# business_card.net
KiCad netlist of a schematic drawn in EAGLE
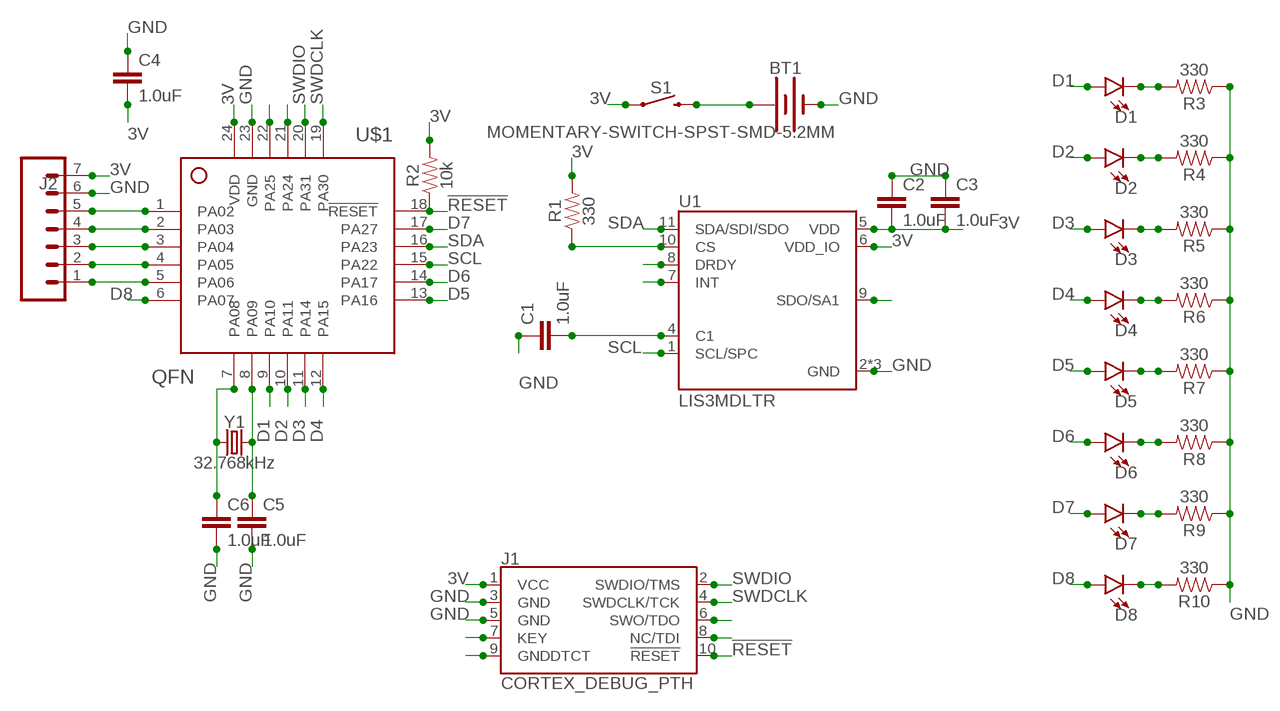
[diagram p0: schematic, sheet 1]

(export (version "E")
  (design (tool "Eeschema 10.0.6"))
  (components
    (comp (ref "BT1")
      (value "BATTERY-20MM_SMD_4LEGS")
      (footprint "eagle-import:BATTCON_20MM_4LEGS")
      (libsource (lib "eagle-import") (part "BATTERY-20MM_SMD_4LEGS"))
    )
    (comp (ref "C1")
      (value "1.0uF")
      (footprint "eagle-import:0402")
      (libsource (lib "eagle-import") (part "1.0UF-0402-16V-10%"))
    )
    (comp (ref "C2")
      (value "1.0uF")
      (footprint "eagle-import:0402")
      (libsource (lib "eagle-import") (part "1.0UF-0402-16V-10%"))
    )
    (comp (ref "C3")
      (value "1.0uF")
      (footprint "eagle-import:0402")
      (libsource (lib "eagle-import") (part "1.0UF-0402-16V-10%"))
    )
    (comp (ref "C4")
      (value "1.0uF")
      (footprint "eagle-import:0402")
      (libsource (lib "eagle-import") (part "1.0UF-0402-16V-10%"))
    )
    (comp (ref "C5")
      (value "1.0uF")
      (footprint "eagle-import:0402")
      (libsource (lib "eagle-import") (part "1.0UF-0402-16V-10%"))
    )
    (comp (ref "C6")
      (value "1.0uF")
      (footprint "eagle-import:0402")
      (libsource (lib "eagle-import") (part "1.0UF-0402-16V-10%"))
    )
    (comp (ref "D1")
      (value "LED0603")
      (footprint "eagle-import:LED-0603")
      (libsource (lib "eagle-import") (part "LED0603"))
    )
    (comp (ref "D2")
      (value "LED0603")
      (footprint "eagle-import:LED-0603")
      (libsource (lib "eagle-import") (part "LED0603"))
    )
    (comp (ref "D3")
      (value "LED0603")
      (footprint "eagle-import:LED-0603")
      (libsource (lib "eagle-import") (part "LED0603"))
    )
    (comp (ref "D4")
      (value "LED0603")
      (footprint "eagle-import:LED-0603")
      (libsource (lib "eagle-import") (part "LED0603"))
    )
    (comp (ref "D5")
      (value "LED0603")
      (footprint "eagle-import:LED-0603")
      (libsource (lib "eagle-import") (part "LED0603"))
    )
    (comp (ref "D6")
      (value "LED0603")
      (footprint "eagle-import:LED-0603")
      (libsource (lib "eagle-import") (part "LED0603"))
    )
    (comp (ref "D7")
      (value "LED0603")
      (footprint "eagle-import:LED-0603")
      (libsource (lib "eagle-import") (part "LED0603"))
    )
    (comp (ref "D8")
      (value "LED0603")
      (footprint "eagle-import:LED-0603")
      (libsource (lib "eagle-import") (part "LED0603"))
    )
    (comp (ref "J1")
      (value "CORTEX_DEBUG_PTH")
      (footprint "eagle-import:2X5-PTH-1.27MM")
      (libsource (lib "eagle-import") (part "CORTEX_DEBUG_PTH"))
    )
    (comp (ref "J2")
      (value "CONN_07")
      (footprint "eagle-import:1X07")
      (libsource (lib "eagle-import") (part "CONN_07"))
    )
    (comp (ref "R1")
      (value "330")
      (footprint "eagle-import:0603")
      (libsource (lib "eagle-import") (part "330OHM-0603-1/10W-1%"))
    )
    (comp (ref "R2")
      (value "10k")
      (footprint "eagle-import:0603")
      (libsource (lib "eagle-import") (part "330OHM-0603-1/10W-1%"))
    )
    (comp (ref "R3")
      (value "330")
      (footprint "eagle-import:0603")
      (libsource (lib "eagle-import") (part "330OHM-0603-1/10W-1%"))
    )
    (comp (ref "R4")
      (value "330")
      (footprint "eagle-import:0603")
      (libsource (lib "eagle-import") (part "330OHM-0603-1/10W-1%"))
    )
    (comp (ref "R5")
      (value "330")
      (footprint "eagle-import:0603")
      (libsource (lib "eagle-import") (part "330OHM-0603-1/10W-1%"))
    )
    (comp (ref "R6")
      (value "330")
      (footprint "eagle-import:0603")
      (libsource (lib "eagle-import") (part "330OHM-0603-1/10W-1%"))
    )
    (comp (ref "R7")
      (value "330")
      (footprint "eagle-import:0603")
      (libsource (lib "eagle-import") (part "330OHM-0603-1/10W-1%"))
    )
    (comp (ref "R8")
      (value "330")
      (footprint "eagle-import:0603")
      (libsource (lib "eagle-import") (part "330OHM-0603-1/10W-1%"))
    )
    (comp (ref "R9")
      (value "330")
      (footprint "eagle-import:0603")
      (libsource (lib "eagle-import") (part "330OHM-0603-1/10W-1%"))
    )
    (comp (ref "R10")
      (value "330")
      (footprint "eagle-import:0603")
      (libsource (lib "eagle-import") (part "330OHM-0603-1/10W-1%"))
    )
    (comp (ref "S1")
      (value "MOMENTARY-SWITCH-SPST-SMD-5.2MM")
      (footprint "eagle-import:TACTILE_SWITCH_SMD_5.2MM")
      (libsource (lib "eagle-import") (part "MOMENTARY-SWITCH-SPST-SMD-5.2MM"))
    )
    (comp (ref "U$1")
      (value "QFN")
      (footprint "eagle-import:QFN24-4X4")
      (libsource (lib "eagle-import") (part "QFN"))
    )
    (comp (ref "U1")
      (value "LIS3MDLTR")
      (footprint "eagle-import:LGA12R50P4X4_200X200X100")
      (fields (field (name "MF") "STMicroelectronics"))
      (libsource (lib "eagle-import") (part "LIS3MDLTR"))
    )
    (comp (ref "Y1")
      (value "32.768kHz")
      (footprint "eagle-import:CRYSTAL-SMD-3.2X1.5MM")
      (libsource (lib "eagle-import") (part "CRYSTAL-32.768KHZSMD-3.2X1.5"))
    )
  )
  (nets
    (net (code "1") (name "/3V") (class "Default")
      (node (ref "C2") (pin "2") (pinfunction "2_2") (pintype "passive"))
      (node (ref "C3") (pin "2") (pinfunction "2_2") (pintype "passive"))
      (node (ref "C4") (pin "2") (pinfunction "2_2") (pintype "passive"))
      (node (ref "J1") (pin "1") (pinfunction "VCC_1") (pintype "bidirectional"))
      (node (ref "J2") (pin "7") (pinfunction "7_7") (pintype "passive"))
      (node (ref "R1") (pin "2") (pinfunction "2_2") (pintype "passive"))
      (node (ref "R2") (pin "2") (pinfunction "2_2") (pintype "passive"))
      (node (ref "S1") (pin "1") (pinfunction "1_1") (pintype "passive"))
      (node (ref "U$1") (pin "24") (pinfunction "VDD_24") (pintype "bidirectional"))
      (node (ref "U1") (pin "5") (pinfunction "VDD_5") (pintype "power_in"))
      (node (ref "U1") (pin "6") (pinfunction "VDD_IO_6") (pintype "power_in"))
    )
    (net (code "2") (name "/D1") (class "Default")
      (node (ref "D1") (pin "A") (pinfunction "A_A") (pintype "passive"))
      (node (ref "U$1") (pin "9") (pinfunction "PA10_9") (pintype "bidirectional"))
    )
    (net (code "3") (name "/D2") (class "Default")
      (node (ref "D2") (pin "A") (pinfunction "A_A") (pintype "passive"))
      (node (ref "U$1") (pin "10") (pinfunction "PA11_10") (pintype "bidirectional"))
    )
    (net (code "4") (name "/D3") (class "Default")
      (node (ref "D3") (pin "A") (pinfunction "A_A") (pintype "passive"))
      (node (ref "U$1") (pin "11") (pinfunction "PA14_11") (pintype "bidirectional"))
    )
    (net (code "5") (name "/D4") (class "Default")
      (node (ref "D4") (pin "A") (pinfunction "A_A") (pintype "passive"))
      (node (ref "U$1") (pin "12") (pinfunction "PA15_12") (pintype "bidirectional"))
    )
    (net (code "6") (name "/D5") (class "Default")
      (node (ref "D5") (pin "A") (pinfunction "A_A") (pintype "passive"))
      (node (ref "U$1") (pin "13") (pinfunction "PA16_13") (pintype "bidirectional"))
    )
    (net (code "7") (name "/D6") (class "Default")
      (node (ref "D6") (pin "A") (pinfunction "A_A") (pintype "passive"))
      (node (ref "U$1") (pin "14") (pinfunction "PA17_14") (pintype "bidirectional"))
    )
    (net (code "8") (name "/D7") (class "Default")
      (node (ref "D7") (pin "A") (pinfunction "A_A") (pintype "passive"))
      (node (ref "U$1") (pin "17") (pinfunction "PA27_17") (pintype "bidirectional"))
    )
    (net (code "9") (name "/D8") (class "Default")
      (node (ref "D8") (pin "A") (pinfunction "A_A") (pintype "passive"))
      (node (ref "U$1") (pin "6") (pinfunction "PA07_6") (pintype "bidirectional"))
    )
    (net (code "10") (name "/GND") (class "Default")
      (node (ref "BT1") (pin "NEGATIVE") (pinfunction "-_NEGATIVE") (pintype "power_in"))
      (node (ref "C1") (pin "1") (pinfunction "1_1") (pintype "passive"))
      (node (ref "C2") (pin "1") (pinfunction "1_1") (pintype "passive"))
      (node (ref "C3") (pin "1") (pinfunction "1_1") (pintype "passive"))
      (node (ref "C4") (pin "1") (pinfunction "1_1") (pintype "passive"))
      (node (ref "C5") (pin "2") (pinfunction "2_2") (pintype "passive"))
      (node (ref "C6") (pin "2") (pinfunction "2_2") (pintype "passive"))
      (node (ref "J1") (pin "3") (pinfunction "GND_3") (pintype "bidirectional"))
      (node (ref "J1") (pin "5") (pinfunction "GND_5") (pintype "bidirectional"))
      (node (ref "J2") (pin "6") (pinfunction "6_6") (pintype "passive"))
      (node (ref "R10") (pin "1") (pinfunction "1_1") (pintype "passive"))
      (node (ref "R3") (pin "1") (pinfunction "1_1") (pintype "passive"))
      (node (ref "R4") (pin "1") (pinfunction "1_1") (pintype "passive"))
      (node (ref "R5") (pin "1") (pinfunction "1_1") (pintype "passive"))
      (node (ref "R6") (pin "1") (pinfunction "1_1") (pintype "passive"))
      (node (ref "R7") (pin "1") (pinfunction "1_1") (pintype "passive"))
      (node (ref "R8") (pin "1") (pinfunction "1_1") (pintype "passive"))
      (node (ref "R9") (pin "1") (pinfunction "1_1") (pintype "passive"))
      (node (ref "U$1") (pin "23") (pinfunction "GND_23") (pintype "bidirectional"))
      (node (ref "U1") (pin "12") (pinfunction "GND_12") (pintype "power_in"))
      (node (ref "U1") (pin "2") (pinfunction "GND_2") (pintype "power_in"))
      (node (ref "U1") (pin "3") (pinfunction "GND_3") (pintype "power_in"))
    )
    (net (code "11") (name "/SCL") (class "Default")
      (node (ref "U$1") (pin "15") (pinfunction "PA22_15") (pintype "bidirectional"))
      (node (ref "U1") (pin "1") (pinfunction "SCL/SPC_1") (pintype "bidirectional"))
    )
    (net (code "12") (name "/SDA") (class "Default")
      (node (ref "U$1") (pin "16") (pinfunction "PA23_16") (pintype "bidirectional"))
      (node (ref "U1") (pin "11") (pinfunction "SDA/SDI/SDO_11") (pintype "input"))
    )
    (net (code "13") (name "/SWDCLK") (class "Default")
      (node (ref "J1") (pin "4") (pinfunction "SWDCLK/TCK_4") (pintype "bidirectional"))
      (node (ref "U$1") (pin "19") (pinfunction "PA30_19") (pintype "bidirectional"))
    )
    (net (code "14") (name "/SWDIO") (class "Default")
      (node (ref "J1") (pin "2") (pinfunction "SWDIO/TMS_2") (pintype "bidirectional"))
      (node (ref "U$1") (pin "20") (pinfunction "PA31_20") (pintype "bidirectional"))
    )
    (net (code "15") (name "/~{RESET}") (class "Default")
      (node (ref "J1") (pin "10") (pinfunction "~{RESET}_10") (pintype "bidirectional"))
      (node (ref "R2") (pin "1") (pinfunction "1_1") (pintype "passive"))
      (node (ref "U$1") (pin "18") (pinfunction "~{RESET}_18") (pintype "bidirectional"))
    )
    (net (code "16") (name "Net-(D1-PadC)") (class "Default")
      (node (ref "D1") (pin "C") (pinfunction "C_C") (pintype "passive"))
      (node (ref "R3") (pin "2") (pinfunction "2_2") (pintype "passive"))
    )
    (net (code "17") (name "Net-(D2-PadC)") (class "Default")
      (node (ref "D2") (pin "C") (pinfunction "C_C") (pintype "passive"))
      (node (ref "R4") (pin "2") (pinfunction "2_2") (pintype "passive"))
    )
    (net (code "18") (name "Net-(D3-PadC)") (class "Default")
      (node (ref "D3") (pin "C") (pinfunction "C_C") (pintype "passive"))
      (node (ref "R5") (pin "2") (pinfunction "2_2") (pintype "passive"))
    )
    (net (code "19") (name "Net-(D4-PadC)") (class "Default")
      (node (ref "D4") (pin "C") (pinfunction "C_C") (pintype "passive"))
      (node (ref "R6") (pin "2") (pinfunction "2_2") (pintype "passive"))
    )
    (net (code "20") (name "Net-(D5-PadC)") (class "Default")
      (node (ref "D5") (pin "C") (pinfunction "C_C") (pintype "passive"))
      (node (ref "R7") (pin "2") (pinfunction "2_2") (pintype "passive"))
    )
    (net (code "21") (name "Net-(D6-PadC)") (class "Default")
      (node (ref "D6") (pin "C") (pinfunction "C_C") (pintype "passive"))
      (node (ref "R8") (pin "2") (pinfunction "2_2") (pintype "passive"))
    )
    (net (code "22") (name "Net-(D7-PadC)") (class "Default")
      (node (ref "D7") (pin "C") (pinfunction "C_C") (pintype "passive"))
      (node (ref "R9") (pin "2") (pinfunction "2_2") (pintype "passive"))
    )
    (net (code "23") (name "Net-(D8-PadC)") (class "Default")
      (node (ref "D8") (pin "C") (pinfunction "C_C") (pintype "passive"))
      (node (ref "R10") (pin "2") (pinfunction "2_2") (pintype "passive"))
    )
    (net (code "24") (name "Net-(S1-2)") (class "Default")
      (node (ref "BT1") (pin "POSITIVE@1") (pinfunction "+_POSITIVE@1") (pintype "power_in"))
      (node (ref "BT1") (pin "POSITIVE@2") (pinfunction "+_POSITIVE@2") (pintype "power_in"))
      (node (ref "BT1") (pin "POSITIVE@3") (pinfunction "+_POSITIVE@3") (pintype "power_in"))
      (node (ref "BT1") (pin "POSITIVE@4") (pinfunction "+_POSITIVE@4") (pintype "power_in"))
      (node (ref "S1") (pin "3") (pinfunction "2_3") (pintype "passive"))
    )
    (net (code "25") (name "Net-(U$1-PA02)") (class "Default")
      (node (ref "J2") (pin "5") (pinfunction "5_5") (pintype "passive"))
      (node (ref "U$1") (pin "1") (pinfunction "PA02_1") (pintype "bidirectional"))
    )
    (net (code "26") (name "Net-(U$1-PA03)") (class "Default")
      (node (ref "J2") (pin "4") (pinfunction "4_4") (pintype "passive"))
      (node (ref "U$1") (pin "2") (pinfunction "PA03_2") (pintype "bidirectional"))
    )
    (net (code "27") (name "Net-(U$1-PA04)") (class "Default")
      (node (ref "J2") (pin "3") (pinfunction "3_3") (pintype "passive"))
      (node (ref "U$1") (pin "3") (pinfunction "PA04_3") (pintype "bidirectional"))
    )
    (net (code "28") (name "Net-(U$1-PA05)") (class "Default")
      (node (ref "J2") (pin "2") (pinfunction "2_2") (pintype "passive"))
      (node (ref "U$1") (pin "4") (pinfunction "PA05_4") (pintype "bidirectional"))
    )
    (net (code "29") (name "Net-(U$1-PA06)") (class "Default")
      (node (ref "J2") (pin "1") (pinfunction "1_1") (pintype "passive"))
      (node (ref "U$1") (pin "5") (pinfunction "PA06_5") (pintype "bidirectional"))
    )
    (net (code "30") (name "Net-(U$1-PA08)") (class "Default")
      (node (ref "C6") (pin "1") (pinfunction "1_1") (pintype "passive"))
      (node (ref "U$1") (pin "7") (pinfunction "PA08_7") (pintype "bidirectional"))
      (node (ref "Y1") (pin "P$1") (pinfunction "1_P$1") (pintype "passive"))
    )
    (net (code "31") (name "Net-(U$1-PA09)") (class "Default")
      (node (ref "C5") (pin "1") (pinfunction "1_1") (pintype "passive"))
      (node (ref "U$1") (pin "8") (pinfunction "PA09_8") (pintype "bidirectional"))
      (node (ref "Y1") (pin "P$2") (pinfunction "2_P$2") (pintype "passive"))
    )
    (net (code "32") (name "Net-(U1-C1)") (class "Default")
      (node (ref "C1") (pin "2") (pinfunction "2_2") (pintype "passive"))
      (node (ref "U1") (pin "4") (pinfunction "C1_4") (pintype "bidirectional"))
    )
    (net (code "33") (name "Net-(U1-CS)") (class "Default")
      (node (ref "R1") (pin "1") (pinfunction "1_1") (pintype "passive"))
      (node (ref "U1") (pin "10") (pinfunction "CS_10") (pintype "input"))
    )
    (net (code "34") (name "unconnected-(J1-GNDDTCT-Pad9)") (class "Default")
      (node (ref "J1") (pin "9") (pinfunction "GNDDTCT_9") (pintype "bidirectional"))
    )
    (net (code "35") (name "unconnected-(J1-KEY-Pad7)") (class "Default")
      (node (ref "J1") (pin "7") (pinfunction "KEY_7") (pintype "bidirectional"))
    )
    (net (code "36") (name "unconnected-(J1-NC{slash}TDI-Pad8)") (class "Default")
      (node (ref "J1") (pin "8") (pinfunction "NC/TDI_8") (pintype "bidirectional"))
    )
    (net (code "37") (name "unconnected-(J1-SWO{slash}TDO-Pad6)") (class "Default")
      (node (ref "J1") (pin "6") (pinfunction "SWO/TDO_6") (pintype "bidirectional"))
    )
    (net (code "38") (name "unconnected-(U$1-PA24-Pad21)") (class "Default")
      (node (ref "U$1") (pin "21") (pinfunction "PA24_21") (pintype "bidirectional"))
    )
    (net (code "39") (name "unconnected-(U$1-PA25-Pad22)") (class "Default")
      (node (ref "U$1") (pin "22") (pinfunction "PA25_22") (pintype "bidirectional"))
    )
    (net (code "40") (name "unconnected-(U1-DRDY-Pad8)") (class "Default")
      (node (ref "U1") (pin "8") (pinfunction "DRDY_8") (pintype "input"))
    )
    (net (code "41") (name "unconnected-(U1-INT-Pad7)") (class "Default")
      (node (ref "U1") (pin "7") (pinfunction "INT_7") (pintype "input"))
    )
    (net (code "42") (name "unconnected-(U1-SDO{slash}SA1-Pad9)") (class "Default")
      (node (ref "U1") (pin "9") (pinfunction "SDO/SA1_9") (pintype "output"))
    )
  )
)
